# IO.net
KiCad netlist of a schematic drawn in Altium Designer
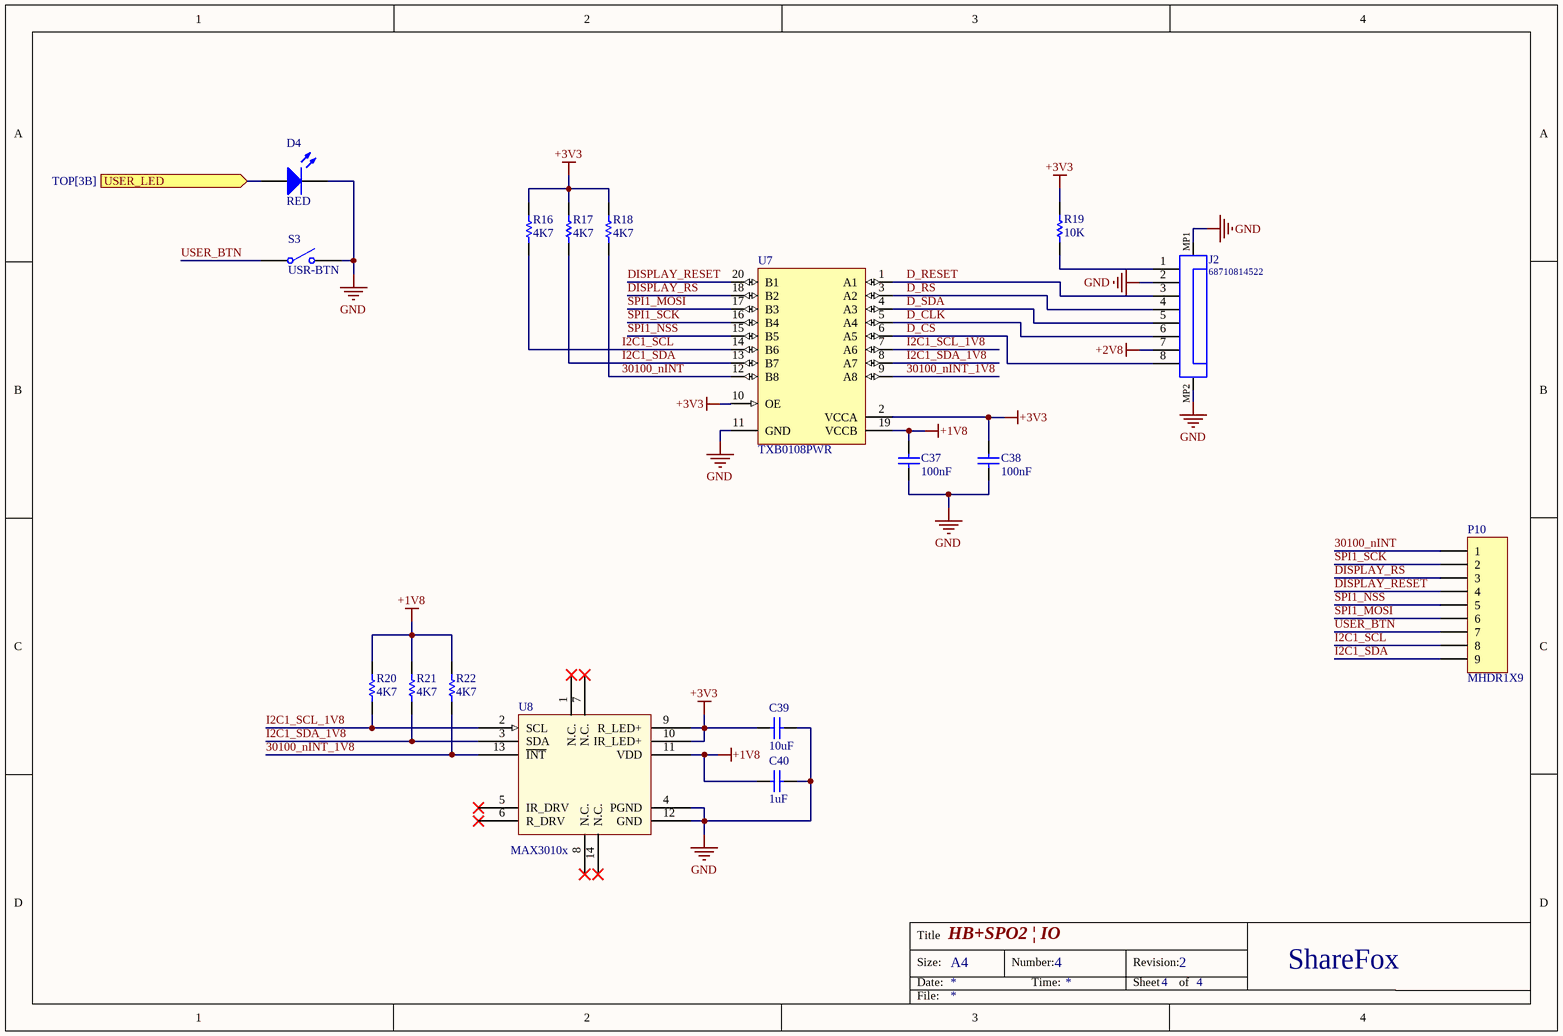
[diagram p0: IO.SchDoc]

(export (version "E")
  (design (tool "Eeschema 10.0.6"))
  (components
    (comp (ref "C37")
      (value "100nF")
      (footprint "C_0603")
      (description "Capacitor")
      (fields (field (name "PUBLISHER") "Altium Limited"))
      (libsource (lib "Miscellaneous Devices") (part "Cap"))
    )
    (comp (ref "C38")
      (value "100nF")
      (footprint "C_0603")
      (description "Capacitor")
      (fields (field (name "PUBLISHER") "Altium Limited"))
      (libsource (lib "Miscellaneous Devices") (part "Cap"))
    )
    (comp (ref "C39")
      (value "10uF")
      (footprint "C_0805")
      (description "Capacitor")
      (fields (field (name "PUBLISHER") "Altium Limited"))
      (libsource (lib "Miscellaneous Devices") (part "Cap"))
    )
    (comp (ref "C40")
      (value "1uF")
      (footprint "C_0603")
      (description "Capacitor")
      (fields (field (name "PUBLISHER") "Altium Limited"))
      (libsource (lib "Miscellaneous Devices") (part "Cap"))
    )
    (comp (ref "D4")
      (value "RED")
      (footprint "D-0603")
      (description "Typical RED, GREEN, YELLOW, AMBER GaAs LED")
      (fields (field (name "PUBLISHER") "Altium Limited"))
      (libsource (lib "Miscellaneous Devices") (part "LED2"))
    )
    (comp (ref "J2")
      (value "68710814522")
      (footprint "68710814522")
      (description "SMT ZIF Connectors WR-FPC, Horizontal, Bottom Contact, pitch 0.5 mm, 8 pins")
      (fields (field (name "MANUFACTURER") "Wurth Elektronik") (field (name "PUBLISHER") "WurthElektronik"))
      (libsource (lib "Altium Content Vault") (part "WE-68X1081XXX22-8"))
    )
    (comp (ref "P10")
      (value "MHDR1X9")
      (footprint "MHDR1X9")
      (description "Header, 9-Pin")
      (fields (field (name "PUBLISHER") "Altium Limited"))
      (libsource (lib "Miscellaneous Connectors") (part "MHDR1X9"))
    )
    (comp (ref "R16")
      (value "4K7")
      (footprint "C_0603")
      (description "Resistor")
      (fields (field (name "PUBLISHER") "Altium Limited"))
      (libsource (lib "Miscellaneous Devices") (part "Res1"))
    )
    (comp (ref "R17")
      (value "4K7")
      (footprint "C_0603")
      (description "Resistor")
      (fields (field (name "PUBLISHER") "Altium Limited"))
      (libsource (lib "Miscellaneous Devices") (part "Res1"))
    )
    (comp (ref "R18")
      (value "4K7")
      (footprint "C_0603")
      (description "Resistor")
      (fields (field (name "PUBLISHER") "Altium Limited"))
      (libsource (lib "Miscellaneous Devices") (part "Res1"))
    )
    (comp (ref "R19")
      (value "10K")
      (footprint "C_0603")
      (description "Resistor")
      (fields (field (name "PUBLISHER") "Altium Limited"))
      (libsource (lib "Miscellaneous Devices") (part "Res1"))
    )
    (comp (ref "R20")
      (value "4K7")
      (footprint "C_0603")
      (description "Resistor")
      (fields (field (name "PUBLISHER") "Altium Limited"))
      (libsource (lib "Miscellaneous Devices") (part "Res1"))
    )
    (comp (ref "R21")
      (value "4K7")
      (footprint "C_0603")
      (description "Resistor")
      (fields (field (name "PUBLISHER") "Altium Limited"))
      (libsource (lib "Miscellaneous Devices") (part "Res1"))
    )
    (comp (ref "R22")
      (value "4K7")
      (footprint "C_0603")
      (description "Resistor")
      (fields (field (name "PUBLISHER") "Altium Limited"))
      (libsource (lib "Miscellaneous Devices") (part "Res1"))
    )
    (comp (ref "S3")
      (value "USR-BTN")
      (footprint "HDR1X2")
      (description "Single-Pole, Single-Throw Switch")
      (fields (field (name "PUBLISHER") "Altium Limited"))
      (libsource (lib "Miscellaneous Devices") (part "SW-SPST"))
    )
    (comp (ref "U7")
      (value "TXB0108PWR")
      (footprint "PW0020A_L")
      (fields (field (name "MANUFACTURER") "Texas Instruments"))
      (libsource (lib "Altium Content Vault") (part "TI-TXB0108-PW-20"))
    )
    (comp (ref "U8")
      (value "MAX3010x")
      (footprint "OESIP14R560x330")
      (description "Pulse Oximeter and Heart-Rate Sensor IC  for Wearable Health")
      (libsource (lib "Max") (part "MAX3010x"))
    )
  )
  (nets
    (net (code "1") (name "+1V8") (class "Default")
      (node (ref "C37") (pin "2") (pinfunction "2_2") (pintype "passive"))
      (node (ref "C40") (pin "2") (pinfunction "2_2") (pintype "passive"))
      (node (ref "R20") (pin "2") (pinfunction "2_2") (pintype "passive"))
      (node (ref "R21") (pin "2") (pinfunction "2_2") (pintype "passive"))
      (node (ref "R22") (pin "2") (pinfunction "2_2") (pintype "passive"))
      (node (ref "U7") (pin "19") (pinfunction "VCCB_19") (pintype "power_in"))
      (node (ref "U8") (pin "11") (pinfunction "VDD_11") (pintype "power_in"))
    )
    (net (code "2") (name "+2V8") (class "Default")
      (node (ref "J2") (pin "7") (pinfunction "7_7") (pintype "passive"))
    )
    (net (code "3") (name "+3V3") (class "Default")
      (node (ref "C38") (pin "2") (pinfunction "2_2") (pintype "passive"))
      (node (ref "C39") (pin "2") (pinfunction "2_2") (pintype "passive"))
      (node (ref "R16") (pin "2") (pinfunction "2_2") (pintype "passive"))
      (node (ref "R17") (pin "2") (pinfunction "2_2") (pintype "passive"))
      (node (ref "R18") (pin "2") (pinfunction "2_2") (pintype "passive"))
      (node (ref "R19") (pin "1") (pinfunction "1_1") (pintype "passive"))
      (node (ref "U7") (pin "10") (pinfunction "OE_10") (pintype "input"))
      (node (ref "U7") (pin "2") (pinfunction "VCCA_2") (pintype "power_in"))
      (node (ref "U8") (pin "10") (pinfunction "IR_LED+_10") (pintype "power_in"))
      (node (ref "U8") (pin "9") (pinfunction "R_LED+_9") (pintype "power_in"))
    )
    (net (code "4") (name "/30100_nINT") (class "Default")
      (node (ref "P10") (pin "1") (pinfunction "1_1") (pintype "passive"))
      (node (ref "R18") (pin "1") (pinfunction "1_1") (pintype "passive"))
      (node (ref "U7") (pin "12") (pinfunction "B8_12") (pintype "bidirectional"))
    )
    (net (code "5") (name "/30100_nINT_1V8") (class "Default")
      (node (ref "R22") (pin "1") (pinfunction "1_1") (pintype "passive"))
      (node (ref "U7") (pin "9") (pinfunction "A8_9") (pintype "bidirectional"))
      (node (ref "U8") (pin "13") (pinfunction "~{INT}_13") (pintype "open_collector"))
    )
    (net (code "6") (name "/DISPLAY_RESET") (class "Default")
      (node (ref "P10") (pin "4") (pinfunction "4_4") (pintype "passive"))
      (node (ref "U7") (pin "20") (pinfunction "B1_20") (pintype "bidirectional"))
    )
    (net (code "7") (name "/DISPLAY_RS") (class "Default")
      (node (ref "P10") (pin "3") (pinfunction "3_3") (pintype "passive"))
      (node (ref "U7") (pin "18") (pinfunction "B2_18") (pintype "bidirectional"))
    )
    (net (code "8") (name "/D_CLK") (class "Default")
      (node (ref "J2") (pin "6") (pinfunction "6_6") (pintype "passive"))
      (node (ref "U7") (pin "5") (pinfunction "A4_5") (pintype "bidirectional"))
    )
    (net (code "9") (name "/D_CS") (class "Default")
      (node (ref "J2") (pin "8") (pinfunction "8_8") (pintype "passive"))
      (node (ref "U7") (pin "6") (pinfunction "A5_6") (pintype "bidirectional"))
    )
    (net (code "10") (name "/D_RESET") (class "Default")
      (node (ref "J2") (pin "3") (pinfunction "3_3") (pintype "passive"))
      (node (ref "U7") (pin "1") (pinfunction "A1_1") (pintype "bidirectional"))
    )
    (net (code "11") (name "/D_RS") (class "Default")
      (node (ref "J2") (pin "4") (pinfunction "4_4") (pintype "passive"))
      (node (ref "U7") (pin "3") (pinfunction "A2_3") (pintype "bidirectional"))
    )
    (net (code "12") (name "/D_SDA") (class "Default")
      (node (ref "J2") (pin "5") (pinfunction "5_5") (pintype "passive"))
      (node (ref "U7") (pin "4") (pinfunction "A3_4") (pintype "bidirectional"))
    )
    (net (code "13") (name "/I2C1_SCL") (class "Default")
      (node (ref "P10") (pin "8") (pinfunction "8_8") (pintype "passive"))
      (node (ref "R16") (pin "1") (pinfunction "1_1") (pintype "passive"))
      (node (ref "U7") (pin "14") (pinfunction "B6_14") (pintype "bidirectional"))
    )
    (net (code "14") (name "/I2C1_SCL_1V8") (class "Default")
      (node (ref "R20") (pin "1") (pinfunction "1_1") (pintype "passive"))
      (node (ref "U7") (pin "7") (pinfunction "A6_7") (pintype "bidirectional"))
      (node (ref "U8") (pin "2") (pinfunction "SCL_2") (pintype "input"))
    )
    (net (code "15") (name "/I2C1_SDA") (class "Default")
      (node (ref "P10") (pin "9") (pinfunction "9_9") (pintype "passive"))
      (node (ref "R17") (pin "1") (pinfunction "1_1") (pintype "passive"))
      (node (ref "U7") (pin "13") (pinfunction "B7_13") (pintype "bidirectional"))
    )
    (net (code "16") (name "/I2C1_SDA_1V8") (class "Default")
      (node (ref "R21") (pin "1") (pinfunction "1_1") (pintype "passive"))
      (node (ref "U7") (pin "8") (pinfunction "A7_8") (pintype "bidirectional"))
      (node (ref "U8") (pin "3") (pinfunction "SDA_3") (pintype "open_collector"))
    )
    (net (code "17") (name "/SPI1_MOSI") (class "Default")
      (node (ref "P10") (pin "6") (pinfunction "6_6") (pintype "passive"))
      (node (ref "U7") (pin "17") (pinfunction "B3_17") (pintype "bidirectional"))
    )
    (net (code "18") (name "/SPI1_NSS") (class "Default")
      (node (ref "P10") (pin "5") (pinfunction "5_5") (pintype "passive"))
      (node (ref "U7") (pin "15") (pinfunction "B5_15") (pintype "bidirectional"))
    )
    (net (code "19") (name "/SPI1_SCK") (class "Default")
      (node (ref "P10") (pin "2") (pinfunction "2_2") (pintype "passive"))
      (node (ref "U7") (pin "16") (pinfunction "B4_16") (pintype "bidirectional"))
    )
    (net (code "20") (name "/USER_BTN") (class "Default")
      (node (ref "P10") (pin "7") (pinfunction "7_7") (pintype "passive"))
      (node (ref "S3") (pin "1") (pinfunction "COMMON_1") (pintype "passive"))
    )
    (net (code "21") (name "/USER_LED") (class "Default")
      (node (ref "D4") (pin "1") (pinfunction "A_1") (pintype "passive"))
    )
    (net (code "22") (name "GND") (class "Default")
      (node (ref "C37") (pin "1") (pinfunction "1_1") (pintype "passive"))
      (node (ref "C38") (pin "1") (pinfunction "1_1") (pintype "passive"))
      (node (ref "C39") (pin "1") (pinfunction "1_1") (pintype "passive"))
      (node (ref "C40") (pin "1") (pinfunction "1_1") (pintype "passive"))
      (node (ref "D4") (pin "2") (pinfunction "K_2") (pintype "passive"))
      (node (ref "J2") (pin "2") (pinfunction "2_2") (pintype "passive"))
      (node (ref "J2") (pin "MP1") (pinfunction "MP1_MP1") (pintype "passive"))
      (node (ref "J2") (pin "MP2") (pinfunction "MP2_MP2") (pintype "passive"))
      (node (ref "S3") (pin "2") (pinfunction "NO_2") (pintype "passive"))
      (node (ref "U7") (pin "11") (pinfunction "GND_11") (pintype "power_in"))
      (node (ref "U8") (pin "12") (pinfunction "GND_12") (pintype "power_in"))
      (node (ref "U8") (pin "4") (pinfunction "PGND_4") (pintype "power_in"))
    )
    (net (code "23") (name "Net-(J2-Pad1)") (class "Default")
      (node (ref "J2") (pin "1") (pinfunction "1_1") (pintype "passive"))
      (node (ref "R19") (pin "2") (pinfunction "2_2") (pintype "passive"))
    )
    (net (code "24") (name "unconnected-(U8-IR_DRV-Pad5)") (class "Default")
      (node (ref "U8") (pin "5") (pinfunction "IR_DRV_5") (pintype "passive+no_connect"))
    )
    (net (code "25") (name "unconnected-(U8-N.C.-Pad1)") (class "Default")
      (node (ref "U8") (pin "1") (pinfunction "N.C._1") (pintype "passive+no_connect"))
    )
    (net (code "26") (name "unconnected-(U8-N.C.-Pad7)") (class "Default")
      (node (ref "U8") (pin "7") (pinfunction "N.C._7") (pintype "passive+no_connect"))
    )
    (net (code "27") (name "unconnected-(U8-N.C.-Pad8)") (class "Default")
      (node (ref "U8") (pin "8") (pinfunction "N.C._8") (pintype "passive+no_connect"))
    )
    (net (code "28") (name "unconnected-(U8-N.C.-Pad14)") (class "Default")
      (node (ref "U8") (pin "14") (pinfunction "N.C._14") (pintype "passive+no_connect"))
    )
    (net (code "29") (name "unconnected-(U8-R_DRV-Pad6)") (class "Default")
      (node (ref "U8") (pin "6") (pinfunction "R_DRV_6") (pintype "passive+no_connect"))
    )
  )
)
